# avr-dds-signal-generator-mod.net
KiCad netlist of a schematic drawn in EAGLE
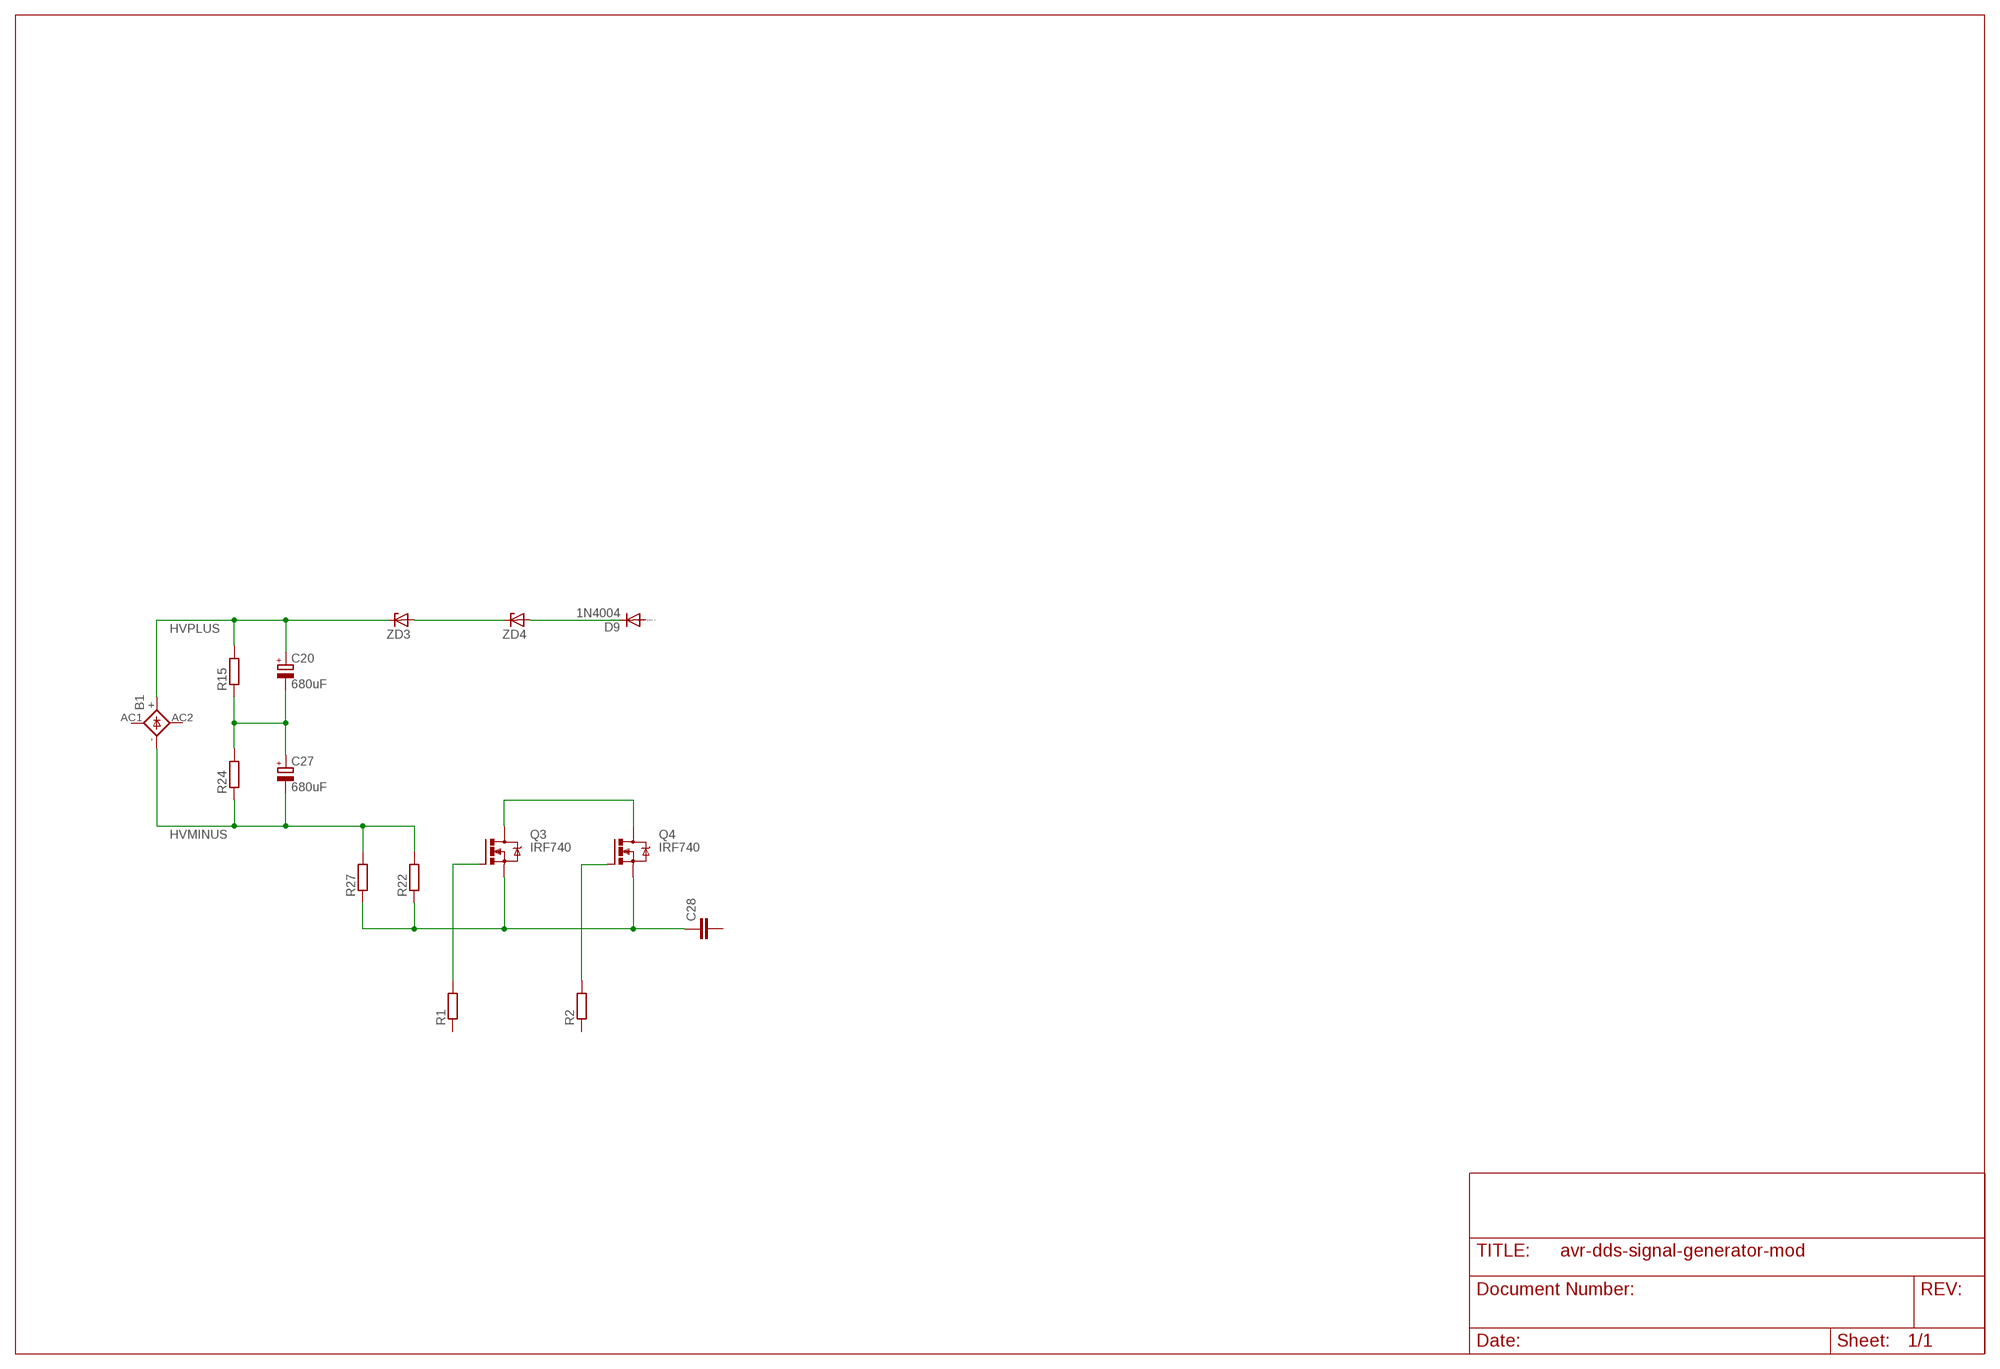
[diagram p0: schematic, sheet 1]

(export (version "E")
  (design (tool "Eeschema 10.0.6"))
  (components
    (comp (ref "B1")
      (value "KBU")
      (footprint "eagle-import:KBU")
      (libsource (lib "eagle-import") (part "KBU"))
    )
    (comp (ref "C20")
      (value "680uF")
      (footprint "eagle-import:EB22,5D")
      (libsource (lib "eagle-import") (part "CPOL-EUE10-22.5"))
    )
    (comp (ref "C27")
      (value "680uF")
      (footprint "eagle-import:EB22,5D")
      (libsource (lib "eagle-import") (part "CPOL-EUE10-22.5"))
    )
    (comp (ref "C28")
      (value "C-EU025-025X050")
      (footprint "eagle-import:C025-025X050")
      (libsource (lib "eagle-import") (part "C-EU025-025X050"))
    )
    (comp (ref "D9")
      (value "1N4004")
      (footprint "eagle-import:DO41-10")
      (libsource (lib "eagle-import") (part "1N4004"))
    )
    (comp (ref "Q3")
      (value "IRF740")
      (footprint "eagle-import:TO220BV")
      (libsource (lib "eagle-import") (part "IRF740"))
    )
    (comp (ref "Q4")
      (value "IRF740")
      (footprint "eagle-import:TO220BV")
      (libsource (lib "eagle-import") (part "IRF740"))
    )
    (comp (ref "R1")
      (value "R-EU_0309/12")
      (footprint "eagle-import:0309_12")
      (libsource (lib "eagle-import") (part "R-EU_0309/12"))
    )
    (comp (ref "R2")
      (value "R-EU_0309/12")
      (footprint "eagle-import:0309_12")
      (libsource (lib "eagle-import") (part "R-EU_0309/12"))
    )
    (comp (ref "R15")
      (value "R-EU_0309/12")
      (footprint "eagle-import:0309_12")
      (libsource (lib "eagle-import") (part "R-EU_0309/12"))
    )
    (comp (ref "R22")
      (value "R-EU_0414/15")
      (footprint "eagle-import:0414_15")
      (libsource (lib "eagle-import") (part "resistor_R-EU_0414/15"))
    )
    (comp (ref "R24")
      (value "R-EU_0309/12")
      (footprint "eagle-import:0309_12")
      (libsource (lib "eagle-import") (part "R-EU_0309/12"))
    )
    (comp (ref "R27")
      (value "R-EU_0414/15")
      (footprint "eagle-import:0414_15")
      (libsource (lib "eagle-import") (part "resistor_R-EU_0414/15"))
    )
    (comp (ref "ZD3")
      (value "ZENER-DIODEC1702-15")
      (footprint "eagle-import:C1702-15")
      (libsource (lib "eagle-import") (part "ZENER-DIODEC1702-15"))
    )
    (comp (ref "ZD4")
      (value "ZENER-DIODEC1702-15")
      (footprint "eagle-import:C1702-15")
      (libsource (lib "eagle-import") (part "ZENER-DIODEC1702-15"))
    )
  )
  (nets
    (net (code "1") (name "/HVMINUS") (class "Default")
      (node (ref "B1") (pin "-") (pinfunction "-_-") (pintype "passive"))
      (node (ref "C27") (pin "-") (pinfunction "-_-") (pintype "passive"))
      (node (ref "R22") (pin "2") (pinfunction "2_2") (pintype "passive"))
      (node (ref "R24") (pin "1") (pinfunction "1_1") (pintype "passive"))
      (node (ref "R27") (pin "2") (pinfunction "2_2") (pintype "passive"))
    )
    (net (code "2") (name "/HVPLUS") (class "Default")
      (node (ref "B1") (pin "+") (pinfunction "+_+") (pintype "passive"))
      (node (ref "C20") (pin "+") (pinfunction "+_+") (pintype "passive"))
      (node (ref "R15") (pin "2") (pinfunction "2_2") (pintype "passive"))
      (node (ref "ZD3") (pin "C") (pinfunction "C_C") (pintype "passive"))
    )
    (net (code "3") (name "Net-(C20-Pad-)") (class "Default")
      (node (ref "C20") (pin "-") (pinfunction "-_-") (pintype "passive"))
      (node (ref "C27") (pin "+") (pinfunction "+_+") (pintype "passive"))
      (node (ref "R15") (pin "1") (pinfunction "1_1") (pintype "passive"))
      (node (ref "R24") (pin "2") (pinfunction "2_2") (pintype "passive"))
    )
    (net (code "4") (name "Net-(C28-Pad1)") (class "Default")
      (node (ref "C28") (pin "1") (pinfunction "1_1") (pintype "passive"))
      (node (ref "Q3") (pin "S") (pinfunction "S_S") (pintype "passive"))
      (node (ref "Q4") (pin "S") (pinfunction "S_S") (pintype "passive"))
      (node (ref "R22") (pin "1") (pinfunction "1_1") (pintype "passive"))
      (node (ref "R27") (pin "1") (pinfunction "1_1") (pintype "passive"))
    )
    (net (code "5") (name "Net-(D9-PadC)") (class "Default")
      (node (ref "D9") (pin "C") (pinfunction "C_C") (pintype "passive"))
      (node (ref "ZD4") (pin "A") (pinfunction "A_A") (pintype "passive"))
    )
    (net (code "6") (name "Net-(Q3-PadD)") (class "Default")
      (node (ref "Q3") (pin "D") (pinfunction "D_D") (pintype "passive"))
      (node (ref "Q4") (pin "D") (pinfunction "D_D") (pintype "passive"))
    )
    (net (code "7") (name "Net-(Q3-PadG)") (class "Default")
      (node (ref "Q3") (pin "G") (pinfunction "G_G") (pintype "passive"))
      (node (ref "R1") (pin "2") (pinfunction "2_2") (pintype "passive"))
    )
    (net (code "8") (name "Net-(Q4-PadG)") (class "Default")
      (node (ref "Q4") (pin "G") (pinfunction "G_G") (pintype "passive"))
      (node (ref "R2") (pin "2") (pinfunction "2_2") (pintype "passive"))
    )
    (net (code "9") (name "Net-(ZD3-PadA)") (class "Default")
      (node (ref "ZD3") (pin "A") (pinfunction "A_A") (pintype "passive"))
      (node (ref "ZD4") (pin "C") (pinfunction "C_C") (pintype "passive"))
    )
    (net (code "10") (name "unconnected-(B1-PadAC1)") (class "Default")
      (node (ref "B1") (pin "AC1") (pinfunction "AC1_AC1") (pintype "passive"))
    )
    (net (code "11") (name "unconnected-(B1-PadAC2)") (class "Default")
      (node (ref "B1") (pin "AC2") (pinfunction "AC2_AC2") (pintype "passive"))
    )
    (net (code "12") (name "unconnected-(C28-Pad2)") (class "Default")
      (node (ref "C28") (pin "2") (pinfunction "2_2") (pintype "passive"))
    )
    (net (code "13") (name "unconnected-(D9-PadA)") (class "Default")
      (node (ref "D9") (pin "A") (pinfunction "A_A") (pintype "passive"))
    )
    (net (code "14") (name "unconnected-(R1-Pad1)") (class "Default")
      (node (ref "R1") (pin "1") (pinfunction "1_1") (pintype "passive"))
    )
    (net (code "15") (name "unconnected-(R2-Pad1)") (class "Default")
      (node (ref "R2") (pin "1") (pinfunction "1_1") (pintype "passive"))
    )
  )
)
